# TMP_1_0.net
KiCad netlist of a schematic drawn in EAGLE
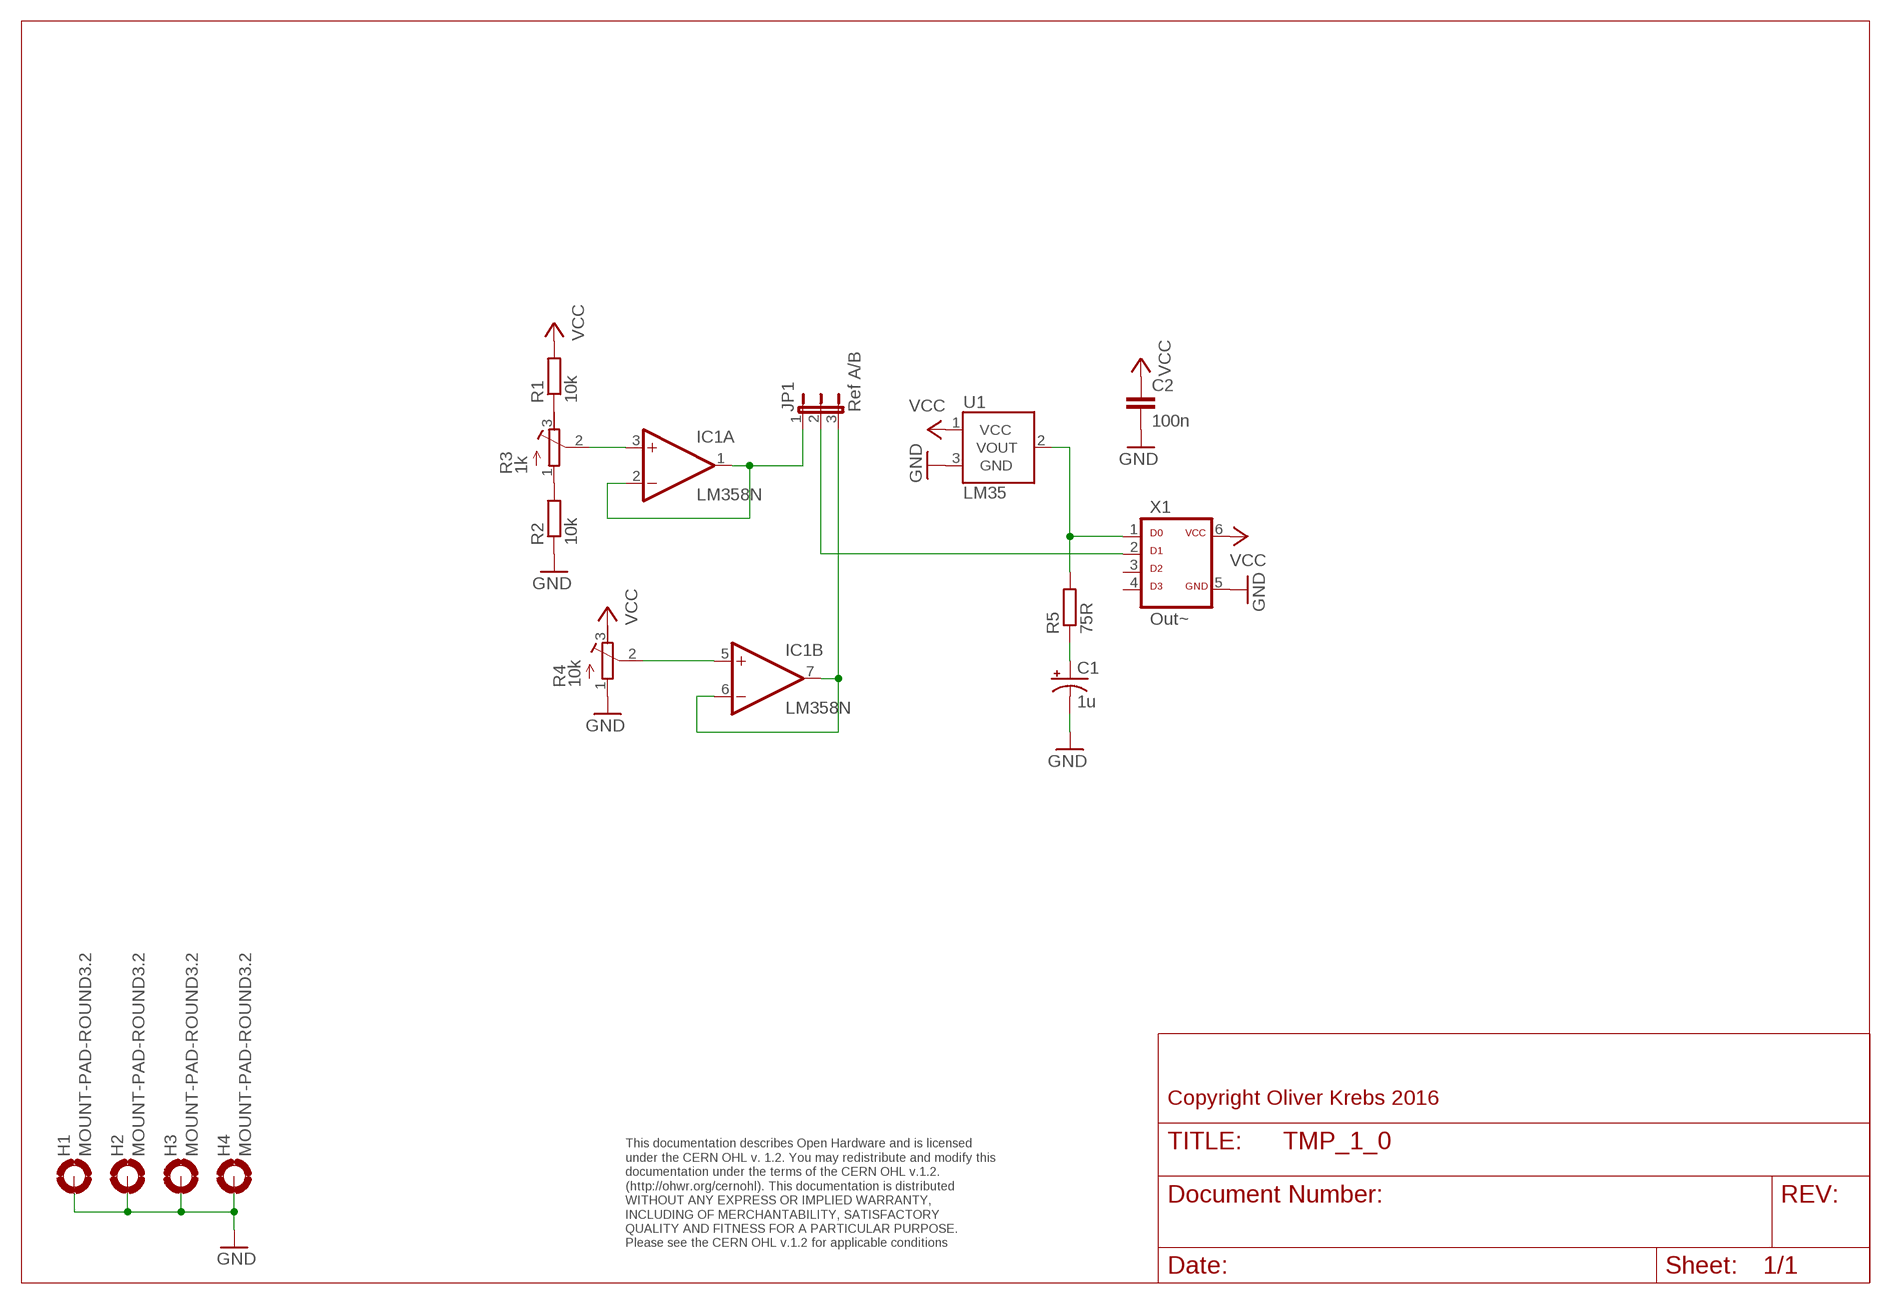
[diagram p0: schematic, sheet 1]

(export (version "E")
  (design (tool "Eeschema 10.0.6"))
  (components
    (comp (ref "C1")
      (value "1u")
      (footprint "eagle-import:CPOL-RADIAL-10UF-25V")
      (libsource (lib "eagle-import") (part "CAP_POLPTH2"))
    )
    (comp (ref "C2")
      (value "100n")
      (footprint "eagle-import:C050-025X075")
      (libsource (lib "eagle-import") (part "C-EU050-025X075"))
    )
    (comp (ref "H1")
      (value "MOUNT-PAD-ROUND3.2")
      (footprint "eagle-import:3,2-PAD")
      (libsource (lib "eagle-import") (part "MOUNT-PAD-ROUND3.2"))
    )
    (comp (ref "H2")
      (value "MOUNT-PAD-ROUND3.2")
      (footprint "eagle-import:3,2-PAD")
      (libsource (lib "eagle-import") (part "MOUNT-PAD-ROUND3.2"))
    )
    (comp (ref "H3")
      (value "MOUNT-PAD-ROUND3.2")
      (footprint "eagle-import:3,2-PAD")
      (libsource (lib "eagle-import") (part "MOUNT-PAD-ROUND3.2"))
    )
    (comp (ref "H4")
      (value "MOUNT-PAD-ROUND3.2")
      (footprint "eagle-import:3,2-PAD")
      (libsource (lib "eagle-import") (part "MOUNT-PAD-ROUND3.2"))
    )
    (comp (ref "IC1")
      (value "LM358N")
      (footprint "eagle-import:DIL08")
      (libsource (lib "eagle-import") (part "LM358N"))
    )
    (comp (ref "JP1")
      (value "Ref A/B")
      (footprint "eagle-import:JP2-U")
      (libsource (lib "eagle-import") (part "JP2EJP2-U"))
    )
    (comp (ref "R1")
      (value "10k")
      (footprint "eagle-import:0207_10")
      (libsource (lib "eagle-import") (part "R-EU_0207/10"))
    )
    (comp (ref "R2")
      (value "10k")
      (footprint "eagle-import:0207_10")
      (libsource (lib "eagle-import") (part "R-EU_0207/10"))
    )
    (comp (ref "R3")
      (value "1k")
      (footprint "eagle-import:ACP-6L")
      (libsource (lib "eagle-import") (part "R-TRIMMACP"))
    )
    (comp (ref "R4")
      (value "10k")
      (footprint "eagle-import:ACP-6L")
      (libsource (lib "eagle-import") (part "R-TRIMMACP"))
    )
    (comp (ref "R5")
      (value "75R")
      (footprint "eagle-import:0207_10")
      (libsource (lib "eagle-import") (part "R-EU_0207/10"))
    )
    (comp (ref "U1")
      (value "LM35")
      (footprint "eagle-import:TO-92")
      (libsource (lib "eagle-import") (part "TMP36GT9"))
    )
    (comp (ref "X1")
      (value "Out~")
      (footprint "eagle-import:ML-6")
      (libsource (lib "eagle-import") (part "ML6D"))
    )
  )
  (nets
    (net (code "1") (name "GND") (class "Default")
      (node (ref "C1") (pin "2") (pinfunction "-_2") (pintype "passive"))
      (node (ref "C2") (pin "2") (pinfunction "2_2") (pintype "passive"))
      (node (ref "H1") (pin "B3,2") (pinfunction "MOUNT_B3,2") (pintype "passive"))
      (node (ref "H2") (pin "B3,2") (pinfunction "MOUNT_B3,2") (pintype "passive"))
      (node (ref "H3") (pin "B3,2") (pinfunction "MOUNT_B3,2") (pintype "passive"))
      (node (ref "H4") (pin "B3,2") (pinfunction "MOUNT_B3,2") (pintype "passive"))
      (node (ref "R2") (pin "1") (pinfunction "1_1") (pintype "passive"))
      (node (ref "R4") (pin "1") (pinfunction "A_1") (pintype "passive"))
      (node (ref "U1") (pin "3") (pinfunction "GND_3") (pintype "bidirectional"))
      (node (ref "X1") (pin "5") (pinfunction "5_5") (pintype "passive"))
    )
    (net (code "2") (name "Net-(C1-+)") (class "Default")
      (node (ref "C1") (pin "1") (pinfunction "+_1") (pintype "passive"))
      (node (ref "R5") (pin "1") (pinfunction "1_1") (pintype "passive"))
    )
    (net (code "3") (name "Net-(IC1A-+IN)") (class "Default")
      (node (ref "IC1") (pin "3") (pinfunction "+IN_3") (pintype "input"))
      (node (ref "R3") (pin "2") (pinfunction "S_2") (pintype "passive"))
    )
    (net (code "4") (name "Net-(IC1A--IN)") (class "Default")
      (node (ref "IC1") (pin "1") (pinfunction "OUT_1") (pintype "output"))
      (node (ref "IC1") (pin "2") (pinfunction "-IN_2") (pintype "input"))
      (node (ref "JP1") (pin "1") (pinfunction "1_1") (pintype "passive"))
    )
    (net (code "5") (name "Net-(IC1B-+IN)") (class "Default")
      (node (ref "IC1") (pin "5") (pinfunction "+IN_5") (pintype "input"))
      (node (ref "R4") (pin "2") (pinfunction "S_2") (pintype "passive"))
    )
    (net (code "6") (name "Net-(IC1B--IN)") (class "Default")
      (node (ref "IC1") (pin "6") (pinfunction "-IN_6") (pintype "input"))
      (node (ref "IC1") (pin "7") (pinfunction "OUT_7") (pintype "output"))
      (node (ref "JP1") (pin "3") (pinfunction "3_3") (pintype "passive"))
    )
    (net (code "7") (name "Net-(JP1-Pad2)") (class "Default")
      (node (ref "JP1") (pin "2") (pinfunction "2_2") (pintype "passive"))
      (node (ref "X1") (pin "2") (pinfunction "2_2") (pintype "passive"))
    )
    (net (code "8") (name "Net-(R3-A)") (class "Default")
      (node (ref "R2") (pin "2") (pinfunction "2_2") (pintype "passive"))
      (node (ref "R3") (pin "1") (pinfunction "A_1") (pintype "passive"))
    )
    (net (code "9") (name "Net-(R3-E)") (class "Default")
      (node (ref "R1") (pin "1") (pinfunction "1_1") (pintype "passive"))
      (node (ref "R3") (pin "3") (pinfunction "E_3") (pintype "passive"))
    )
    (net (code "10") (name "Net-(U1-VOUT)") (class "Default")
      (node (ref "R5") (pin "2") (pinfunction "2_2") (pintype "passive"))
      (node (ref "U1") (pin "2") (pinfunction "VOUT_2") (pintype "bidirectional"))
      (node (ref "X1") (pin "1") (pinfunction "1_1") (pintype "passive"))
    )
    (net (code "11") (name "VCC") (class "Default")
      (node (ref "C2") (pin "1") (pinfunction "1_1") (pintype "passive"))
      (node (ref "R1") (pin "2") (pinfunction "2_2") (pintype "passive"))
      (node (ref "R4") (pin "3") (pinfunction "E_3") (pintype "passive"))
      (node (ref "U1") (pin "1") (pinfunction "VCC_1") (pintype "bidirectional"))
      (node (ref "X1") (pin "6") (pinfunction "6_6") (pintype "passive"))
    )
    (net (code "12") (name "unconnected-(X1-Pad3)") (class "Default")
      (node (ref "X1") (pin "3") (pinfunction "3_3") (pintype "passive"))
    )
    (net (code "13") (name "unconnected-(X1-Pad4)") (class "Default")
      (node (ref "X1") (pin "4") (pinfunction "4_4") (pintype "passive"))
    )
  )
)
